# 02_PowerPart.net
KiCad netlist of a schematic drawn in EasyEDA Pro
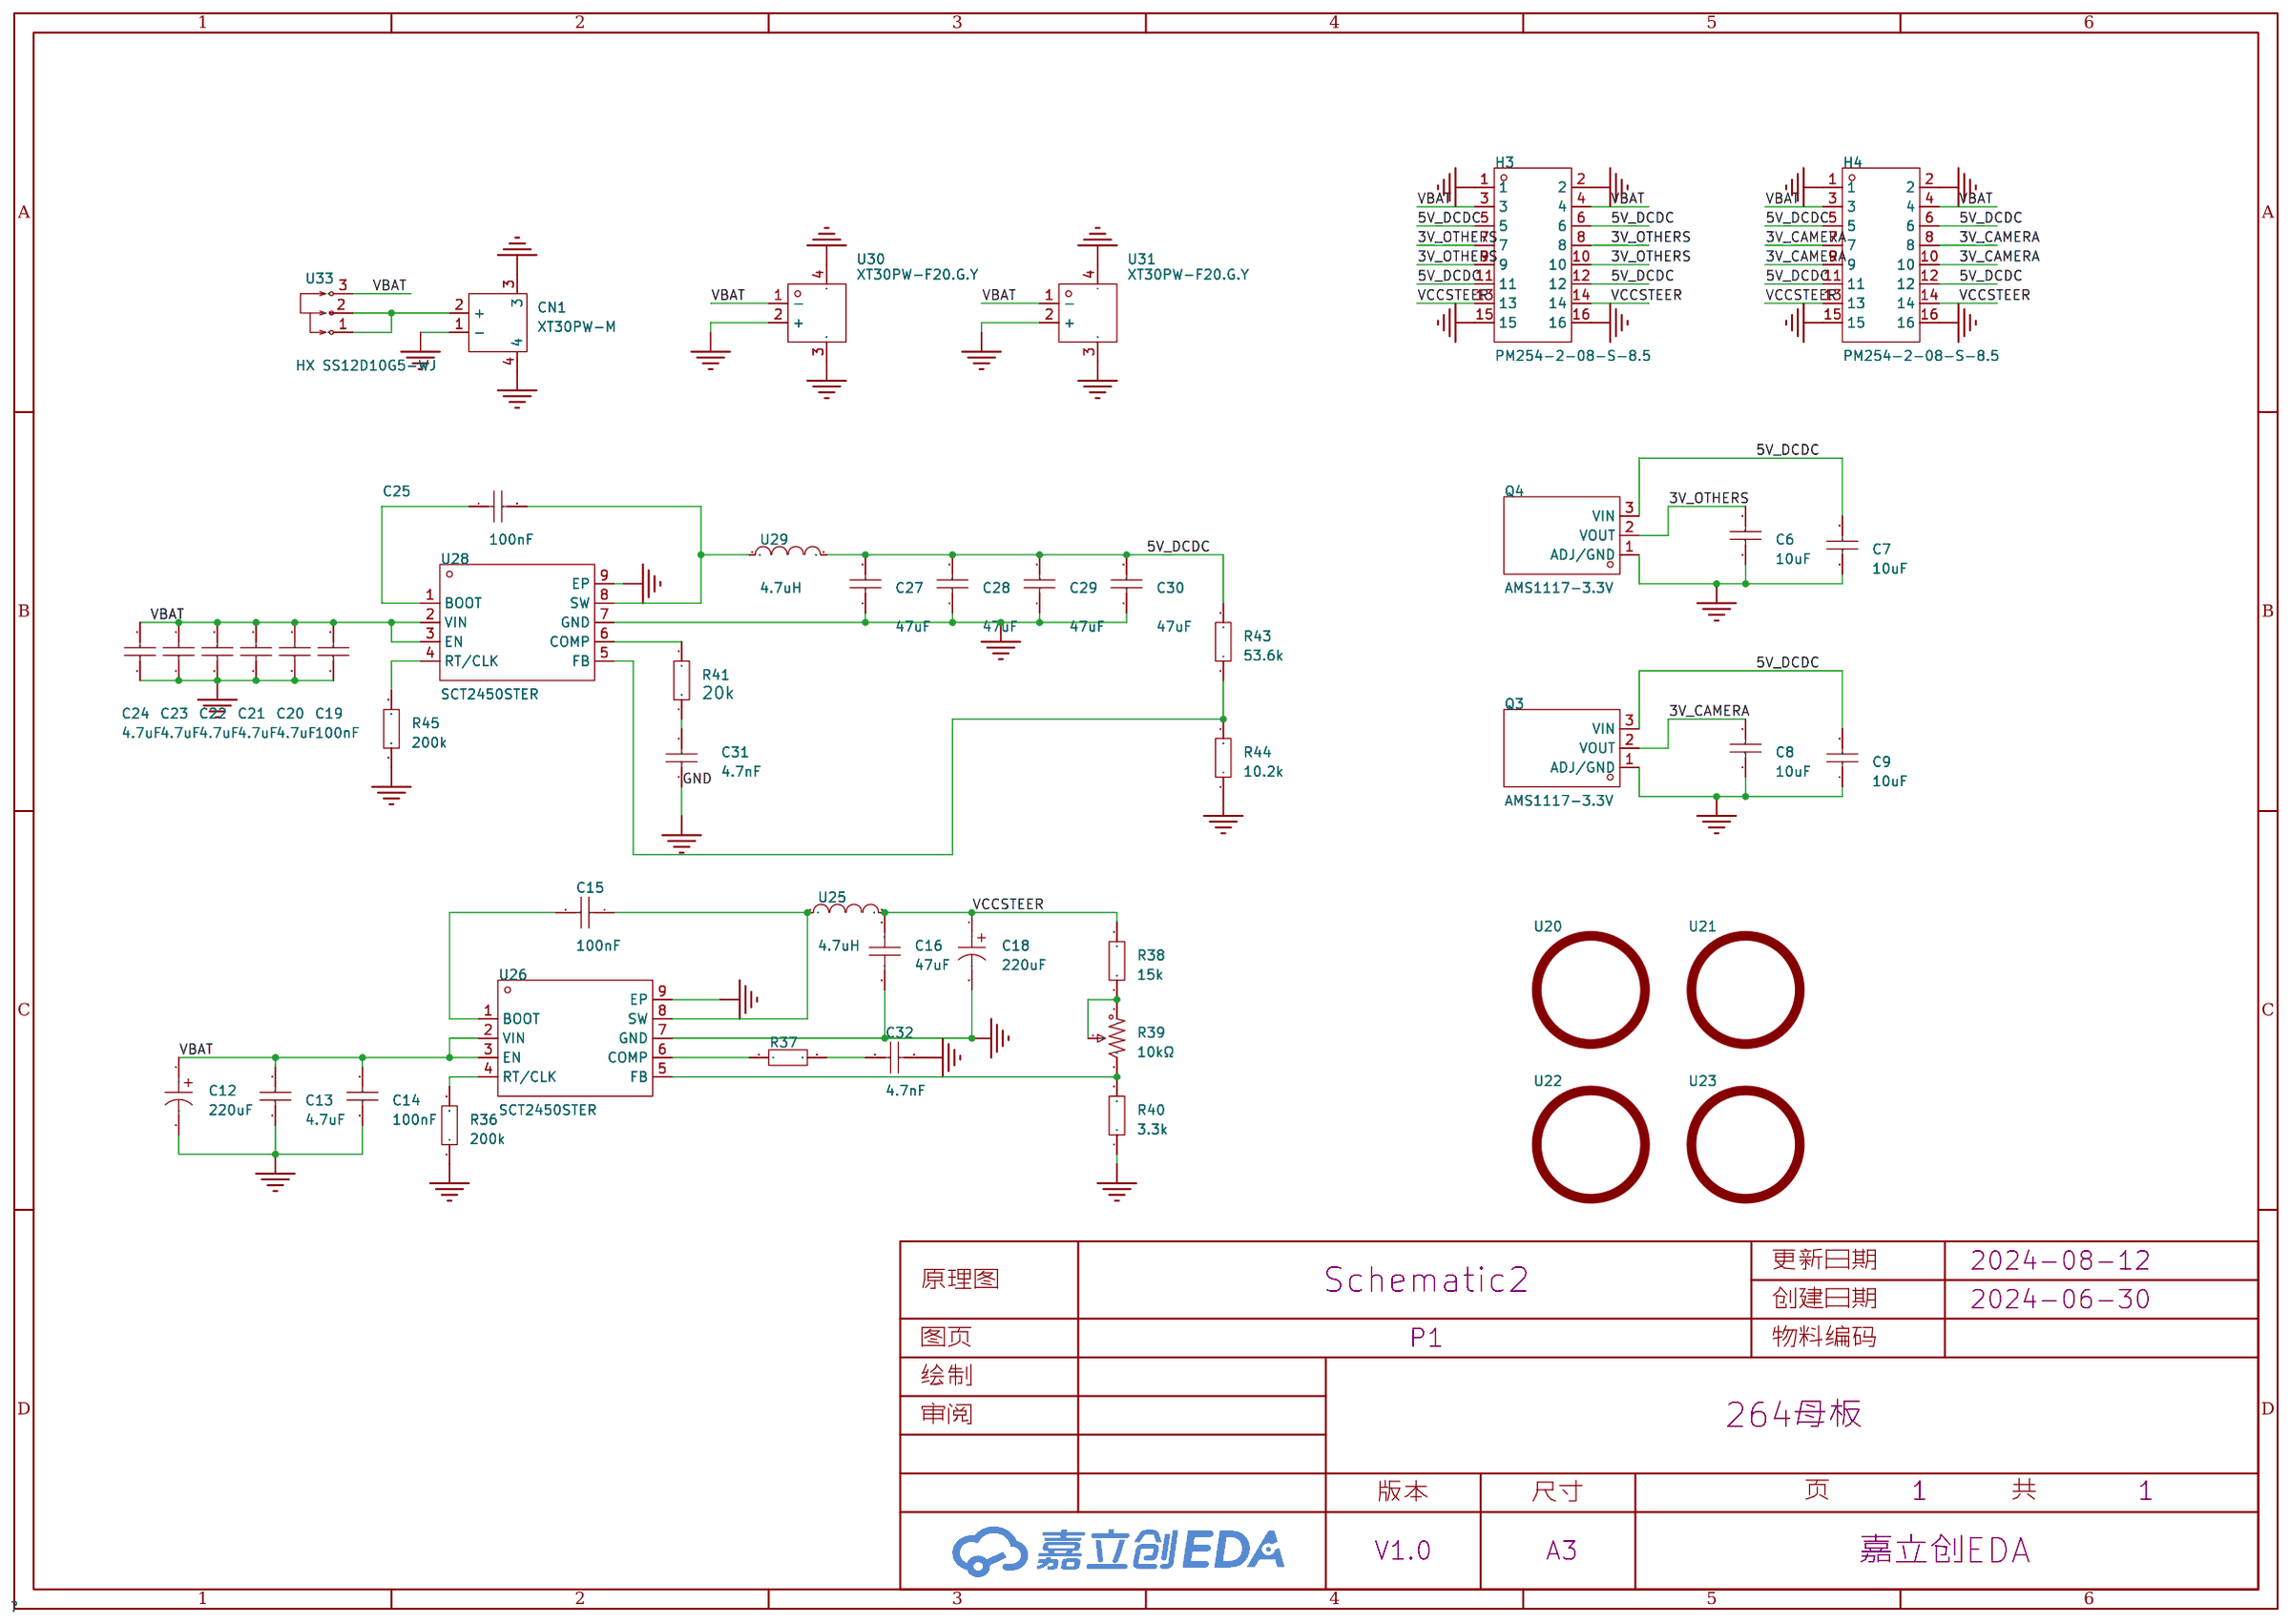
[diagram p0: schematic sheet]

(export (version "E")
  (design (tool "Eeschema 10.0.6"))
  (components
    (comp (ref "C6") (value "10uF") (footprint "easyedapro:C0805") (libsource (lib "easyedapro") (part "电容")))
    (comp (ref "C7") (value "10uF") (footprint "easyedapro:C0805") (libsource (lib "easyedapro") (part "电容")))
    (comp (ref "C8") (value "10uF") (footprint "easyedapro:C0805") (libsource (lib "easyedapro") (part "电容")))
    (comp (ref "C9") (value "10uF") (footprint "easyedapro:C0805") (libsource (lib "easyedapro") (part "电容")))
    (comp (ref "C12")
      (value "220uF")
      (footprint "easyedapro:CAP-SMD_BD6.3-L6.6-W6.6-FD")
      (description "容值:220uF;精度:±20%;额定电压:16V;纹波电流:110mA@120Hz;等效串联电阻:-;")
      (fields
        (field (name "Manufacturer Part") "RVT220UF16V67RV0015")
        (field (name "Manufacturer") "KNSCHA(科尼盛)")
      )
      (libsource (lib "easyedapro") (part "RVT220UF16V67RV0015"))
    )
    (comp (ref "C13")
      (value "4.7uF")
      (footprint "easyedapro:C0805")
      (description "50V")
      (libsource (lib "easyedapro") (part "电容-0805C"))
    )
    (comp (ref "C14")
      (value "100nF")
      (footprint "easyedapro:C0805")
      (libsource (lib "easyedapro") (part "电容-0805C"))
    )
    (comp (ref "C15")
      (value "100nF")
      (footprint "easyedapro:C0805")
      (libsource (lib "easyedapro") (part "电容-0805C"))
    )
    (comp (ref "C16")
      (value "47uF")
      (footprint "easyedapro:C1206")
      (description "容值:47uF;精度:±20%;额定电压:10V;材质(温度系数):X5R;")
      (fields
        (field (name "Manufacturer Part") "CL31A476MPHNNNE")
        (field (name "Manufacturer") "SAMSUNG(三星)")
      )
      (libsource (lib "easyedapro") (part "CL31A476MPHNNNE"))
    )
    (comp (ref "C18")
      (value "220uF")
      (footprint "easyedapro:CAP-SMD_BD6.3-L6.6-W6.6-FD")
      (description "容值:220uF;精度:±20%;额定电压:16V;纹波电流:110mA@120Hz;等效串联电阻:-;")
      (fields
        (field (name "Manufacturer Part") "RVT220UF16V67RV0015")
        (field (name "Manufacturer") "KNSCHA(科尼盛)")
      )
      (libsource (lib "easyedapro") (part "RVT220UF16V67RV0015"))
    )
    (comp (ref "C19")
      (value "100nF")
      (footprint "easyedapro:C0805")
      (libsource (lib "easyedapro") (part "电容-0805C"))
    )
    (comp (ref "C20")
      (value "4.7uF")
      (footprint "easyedapro:C0805")
      (libsource (lib "easyedapro") (part "电容-0805C"))
    )
    (comp (ref "C21")
      (value "4.7uF")
      (footprint "easyedapro:C0805")
      (libsource (lib "easyedapro") (part "电容-0805C"))
    )
    (comp (ref "C22")
      (value "4.7uF")
      (footprint "easyedapro:C0805")
      (libsource (lib "easyedapro") (part "电容-0805C"))
    )
    (comp (ref "C23")
      (value "4.7uF")
      (footprint "easyedapro:C0805")
      (libsource (lib "easyedapro") (part "电容-0805C"))
    )
    (comp (ref "C24")
      (value "4.7uF")
      (footprint "easyedapro:C0805")
      (libsource (lib "easyedapro") (part "电容-0805C"))
    )
    (comp (ref "C25")
      (value "100nF")
      (footprint "easyedapro:C0805")
      (libsource (lib "easyedapro") (part "电容-0805C"))
    )
    (comp (ref "C27")
      (value "47uF")
      (footprint "easyedapro:C0805")
      (libsource (lib "easyedapro") (part "电容-0805C"))
    )
    (comp (ref "C28")
      (value "47uF")
      (footprint "easyedapro:C0805")
      (libsource (lib "easyedapro") (part "电容-0805C"))
    )
    (comp (ref "C29")
      (value "47uF")
      (footprint "easyedapro:C0805")
      (libsource (lib "easyedapro") (part "电容-0805C"))
    )
    (comp (ref "C30")
      (value "47uF")
      (footprint "easyedapro:C0805")
      (libsource (lib "easyedapro") (part "电容-0805C"))
    )
    (comp (ref "C31")
      (value "4.7nF")
      (footprint "easyedapro:C0805")
      (libsource (lib "easyedapro") (part "电容-0805C"))
    )
    (comp (ref "C32")
      (value "4.7nF")
      (footprint "easyedapro:C0805")
      (libsource (lib "easyedapro") (part "电容-0805C"))
    )
    (comp (ref "CN1")
      (value "XT30PW-M")
      (footprint "easyedapro:CONN-TH_XT30PW-M")
      (description "类别:-;类型1:-;")
      (fields (field (name "Manufacturer") "AMASS(艾迈斯)"))
      (libsource (lib "easyedapro") (part "XT30PW-M"))
    )
    (comp (ref "H3")
      (value "PM254-2-08-S-8.5")
      (footprint "easyedapro:HDR-SMD_16P-P2.54-V-F-R2-C8-LS7.1")
      (fields (field (name "Manufacturer") "HCTL(华灿天禄)"))
      (libsource (lib "easyedapro") (part "PM254-2-08-S-8.5"))
    )
    (comp (ref "H4")
      (value "PM254-2-08-S-8.5")
      (footprint "easyedapro:HDR-SMD_16P-P2.54-V-F-R2-C8-LS7.1")
      (fields (field (name "Manufacturer") "HCTL(华灿天禄)"))
      (libsource (lib "easyedapro") (part "PM254-2-08-S-8.5"))
    )
    (comp (ref "Q3")
      (value "AMS1117-3.3V")
      (footprint "easyedapro:SOT-89-3_L4.5-W2.5-P1.50-LS4.2-BR")
      (description "输出类型:固定;最大输入电压:18V;输出电压:3.3V;最大输出电流:1A;输出极性:正极;")
      (fields (field (name "Manufacturer") "MSKSEMI(美森科)"))
      (libsource (lib "easyedapro") (part "AMS1117-3.3V_C5120796"))
    )
    (comp (ref "Q4")
      (value "AMS1117-3.3V")
      (footprint "easyedapro:SOT-89-3_L4.5-W2.5-P1.50-LS4.2-BR")
      (description "输出类型:固定;最大输入电压:18V;输出电压:3.3V;最大输出电流:1A;输出极性:正极;")
      (fields (field (name "Manufacturer") "MSKSEMI(美森科)"))
      (libsource (lib "easyedapro") (part "AMS1117-3.3V_C5120796"))
    )
    (comp (ref "R36")
      (value "200k")
      (footprint "easyedapro:R0805")
      (description "电阻类型:厚膜电阻;阻值:1kΩ;精度:±1%;功率:125mW;温度系数:±100ppm/°C;最大工作电压:150V;工作温度范围:-55°C~+155°C;")
      (libsource (lib "easyedapro") (part "电阻_0805"))
    )
    (comp (ref "R37")
      (value "20k")
      (footprint "easyedapro:R0805")
      (description "电阻类型:厚膜电阻;阻值:1kΩ;精度:±1%;功率:125mW;温度系数:±100ppm/°C;最大工作电压:150V;工作温度范围:-55°C~+155°C;")
      (libsource (lib "easyedapro") (part "电阻_0805"))
    )
    (comp (ref "R38")
      (value "15k")
      (footprint "easyedapro:R0805")
      (description "电阻类型:厚膜电阻;阻值:1kΩ;精度:±1%;功率:125mW;温度系数:±100ppm/°C;最大工作电压:150V;工作温度范围:-55°C~+155°C;")
      (libsource (lib "easyedapro") (part "电阻_0805"))
    )
    (comp (ref "R39")
      (value "10kΩ")
      (footprint "easyedapro:RES-ADJ-TH_3P-L10.0-W10.0-P2.50-L")
      (description "阻值:10kΩ;精度:±10%;")
      (fields (field (name "Manufacturer Part") "3296W-1-103") (field (name "Manufacturer") "BOCHEN(博晨)"))
      (libsource (lib "easyedapro") (part "3296W-1-103"))
    )
    (comp (ref "R40")
      (value "3.3k")
      (footprint "easyedapro:R0805")
      (description "电阻类型:厚膜电阻;阻值:1kΩ;精度:±1%;功率:125mW;温度系数:±100ppm/°C;最大工作电压:150V;工作温度范围:-55°C~+155°C;")
      (libsource (lib "easyedapro") (part "电阻_0805"))
    )
    (comp (ref "R41")
      (value "20k")
      (footprint "easyedapro:R0805")
      (description "电阻类型:厚膜电阻;阻值:1kΩ;精度:±1%;功率:125mW;温度系数:±100ppm/°C;最大工作电压:150V;工作温度范围:-55°C~+155°C;")
      (libsource (lib "easyedapro") (part "电阻_0805"))
    )
    (comp (ref "R43")
      (value "53.6k")
      (footprint "easyedapro:R0603")
      (description "电阻类型:厚膜电阻;阻值:10kΩ;精度:±1%;功率:100mW;最大工作电压:75V;温度系数:±100ppm/°C;")
      (fields
        (field (name "Manufacturer Part") "0603WAF1002T5E")
        (field (name "Manufacturer") "UNI-ROYAL(厚声)")
      )
      (libsource (lib "easyedapro") (part "0603WAF1002T5E"))
    )
    (comp (ref "R44")
      (value "10.2k")
      (footprint "easyedapro:R0603")
      (description "电阻类型:厚膜电阻;阻值:10kΩ;精度:±1%;功率:100mW;最大工作电压:75V;温度系数:±100ppm/°C;")
      (fields
        (field (name "Manufacturer Part") "0603WAF1002T5E")
        (field (name "Manufacturer") "UNI-ROYAL(厚声)")
      )
      (libsource (lib "easyedapro") (part "0603WAF1002T5E"))
    )
    (comp (ref "R45")
      (value "200k")
      (footprint "easyedapro:R0805")
      (description "电阻类型:厚膜电阻;阻值:1kΩ;精度:±1%;功率:125mW;温度系数:±100ppm/°C;最大工作电压:150V;工作温度范围:-55°C~+155°C;")
      (libsource (lib "easyedapro") (part "电阻_0805"))
    )
    (comp (ref "U20") (value "~") (footprint "easyedapro:固定孔") (libsource (lib "easyedapro") (part "固定孔")))
    (comp (ref "U21") (value "~") (footprint "easyedapro:固定孔") (libsource (lib "easyedapro") (part "固定孔")))
    (comp (ref "U22") (value "~") (footprint "easyedapro:固定孔") (libsource (lib "easyedapro") (part "固定孔")))
    (comp (ref "U23") (value "~") (footprint "easyedapro:固定孔") (libsource (lib "easyedapro") (part "固定孔")))
    (comp (ref "U25")
      (value "4.7uH")
      (footprint "easyedapro:IND-SMD_L7.2-W6.6_GPSR07X0")
      (description "电感值:4.7uH;精度:±20%;额定电流:5A;直流电阻(DCR):34.5mΩ;")
      (fields (field (name "Manufacturer Part") "CYA0630-4.7UH") (field (name "Manufacturer") "SHOU HAN(首韩)"))
      (libsource (lib "easyedapro") (part "CYA0630-4.7UH"))
    )
    (comp (ref "U26")
      (value "SCT2450STER")
      (footprint "easyedapro:ESOP-8_L4.9-W3.9-P1.27-LS6.0-BL-EP")
      (fields (field (name "Manufacturer") "SCT(芯洲科技)"))
      (libsource (lib "easyedapro") (part "SCT2450STER"))
    )
    (comp (ref "U28")
      (value "SCT2450STER")
      (footprint "easyedapro:ESOP-8_L4.9-W3.9-P1.27-LS6.0-BL-EP")
      (fields (field (name "Manufacturer") "SCT(芯洲科技)"))
      (libsource (lib "easyedapro") (part "SCT2450STER"))
    )
    (comp (ref "U29")
      (value "4.7uH")
      (footprint "easyedapro:IND-SMD_L7.2-W6.6_GPSR07X0")
      (description "电感值:4.7uH;精度:±20%;额定电流:5A;直流电阻(DCR):34.5mΩ;")
      (fields (field (name "Manufacturer Part") "CYA0630-4.7UH") (field (name "Manufacturer") "SHOU HAN(首韩)"))
      (libsource (lib "easyedapro") (part "CYA0630-4.7UH"))
    )
    (comp (ref "U30")
      (value "XT30PW-F20.G.Y")
      (footprint "easyedapro:CONN-TH_XT30PW-F-1")
      (description "类别:-;类型1:-;")
      (fields (field (name "Manufacturer") "AMASS(艾迈斯)"))
      (libsource (lib "easyedapro") (part "XT30PW-F20.G.Y"))
    )
    (comp (ref "U31")
      (value "XT30PW-F20.G.Y")
      (footprint "easyedapro:CONN-TH_XT30PW-F-1")
      (description "类别:-;类型1:-;")
      (fields (field (name "Manufacturer") "AMASS(艾迈斯)"))
      (libsource (lib "easyedapro") (part "XT30PW-F20.G.Y"))
    )
    (comp (ref "U33")
      (value "HX SS12D10G5-WJ")
      (footprint "easyedapro:SW-TH_3P-P4.80_HX-SS12D10G5-WJ")
      (description "电路结构:单刀双掷;额定电流(DC):2A;额定电压(DC):125V;机械寿命:3千次;")
      (fields (field (name "Manufacturer") "hanxia(韩下)"))
      (libsource (lib "easyedapro") (part "HX SS12D10G5-WJ"))
    )
  )
  (nets
    (net (code "1") (name "/3V_CAMERA") (class "Default")
      (node (ref "C8") (pin "2") (pinfunction "2_2") (pintype "input"))
      (node (ref "H4") (pin "10") (pinfunction "10_10") (pintype "unspecified"))
      (node (ref "H4") (pin "7") (pinfunction "7_7") (pintype "unspecified"))
      (node (ref "H4") (pin "8") (pinfunction "8_8") (pintype "unspecified"))
      (node (ref "H4") (pin "9") (pinfunction "9_9") (pintype "unspecified"))
      (node (ref "Q3") (pin "2") (pinfunction "VOUT_2") (pintype "unspecified"))
    )
    (net (code "2") (name "/3V_OTHERS") (class "Default")
      (node (ref "C6") (pin "2") (pinfunction "2_2") (pintype "input"))
      (node (ref "H3") (pin "10") (pinfunction "10_10") (pintype "unspecified"))
      (node (ref "H3") (pin "7") (pinfunction "7_7") (pintype "unspecified"))
      (node (ref "H3") (pin "8") (pinfunction "8_8") (pintype "unspecified"))
      (node (ref "H3") (pin "9") (pinfunction "9_9") (pintype "unspecified"))
      (node (ref "Q4") (pin "2") (pinfunction "VOUT_2") (pintype "unspecified"))
    )
    (net (code "3") (name "/5V_DCDC") (class "Default")
      (node (ref "C27") (pin "2") (pinfunction "2_2") (pintype "input"))
      (node (ref "C28") (pin "2") (pinfunction "2_2") (pintype "input"))
      (node (ref "C29") (pin "2") (pinfunction "2_2") (pintype "input"))
      (node (ref "C30") (pin "2") (pinfunction "2_2") (pintype "input"))
      (node (ref "C7") (pin "2") (pinfunction "2_2") (pintype "input"))
      (node (ref "C9") (pin "2") (pinfunction "2_2") (pintype "input"))
      (node (ref "H3") (pin "11") (pinfunction "11_11") (pintype "unspecified"))
      (node (ref "H3") (pin "12") (pinfunction "12_12") (pintype "unspecified"))
      (node (ref "H3") (pin "5") (pinfunction "5_5") (pintype "unspecified"))
      (node (ref "H3") (pin "6") (pinfunction "6_6") (pintype "unspecified"))
      (node (ref "H4") (pin "11") (pinfunction "11_11") (pintype "unspecified"))
      (node (ref "H4") (pin "12") (pinfunction "12_12") (pintype "unspecified"))
      (node (ref "H4") (pin "5") (pinfunction "5_5") (pintype "unspecified"))
      (node (ref "H4") (pin "6") (pinfunction "6_6") (pintype "unspecified"))
      (node (ref "Q3") (pin "3") (pinfunction "VIN_3") (pintype "unspecified"))
      (node (ref "Q4") (pin "3") (pinfunction "VIN_3") (pintype "unspecified"))
      (node (ref "R43") (pin "2") (pinfunction "2_2") (pintype "input"))
      (node (ref "U29") (pin "2") (pinfunction "2_2") (pintype "unspecified"))
    )
    (net (code "4") (name "/VBAT") (class "Default")
      (node (ref "C12") (pin "1") (pinfunction "1_1") (pintype "input"))
      (node (ref "C13") (pin "2") (pinfunction "2_2") (pintype "input"))
      (node (ref "C14") (pin "2") (pinfunction "2_2") (pintype "input"))
      (node (ref "C19") (pin "1") (pinfunction "1_1") (pintype "input"))
      (node (ref "C20") (pin "1") (pinfunction "1_1") (pintype "input"))
      (node (ref "C21") (pin "1") (pinfunction "1_1") (pintype "input"))
      (node (ref "C22") (pin "1") (pinfunction "1_1") (pintype "input"))
      (node (ref "C23") (pin "1") (pinfunction "1_1") (pintype "input"))
      (node (ref "C24") (pin "1") (pinfunction "1_1") (pintype "input"))
      (node (ref "H3") (pin "3") (pinfunction "3_3") (pintype "unspecified"))
      (node (ref "H3") (pin "4") (pinfunction "4_4") (pintype "unspecified"))
      (node (ref "H4") (pin "3") (pinfunction "3_3") (pintype "unspecified"))
      (node (ref "H4") (pin "4") (pinfunction "4_4") (pintype "unspecified"))
      (node (ref "U26") (pin "2") (pinfunction "VIN_2") (pintype "input"))
      (node (ref "U26") (pin "3") (pinfunction "EN_3") (pintype "input"))
      (node (ref "U28") (pin "2") (pinfunction "VIN_2") (pintype "input"))
      (node (ref "U28") (pin "3") (pinfunction "EN_3") (pintype "input"))
      (node (ref "U30") (pin "1") (pinfunction "-_1") (pintype "unspecified"))
      (node (ref "U31") (pin "1") (pinfunction "-_1") (pintype "unspecified"))
      (node (ref "U33") (pin "3") (pinfunction "3_3") (pintype "unspecified"))
    )
    (net (code "5") (name "/VCCSTEER") (class "Default")
      (node (ref "C16") (pin "2") (pinfunction "2_2") (pintype "unspecified"))
      (node (ref "C18") (pin "1") (pinfunction "1_1") (pintype "input"))
      (node (ref "H3") (pin "13") (pinfunction "13_13") (pintype "unspecified"))
      (node (ref "H3") (pin "14") (pinfunction "14_14") (pintype "unspecified"))
      (node (ref "H4") (pin "13") (pinfunction "13_13") (pintype "unspecified"))
      (node (ref "H4") (pin "14") (pinfunction "14_14") (pintype "unspecified"))
      (node (ref "R38") (pin "2") (pinfunction "2_2") (pintype "input"))
      (node (ref "U25") (pin "2") (pinfunction "2_2") (pintype "unspecified"))
    )
    (net (code "6") (name "GND") (class "Default")
      (node (ref "C12") (pin "2") (pinfunction "2_2") (pintype "input"))
      (node (ref "C13") (pin "1") (pinfunction "1_1") (pintype "input"))
      (node (ref "C14") (pin "1") (pinfunction "1_1") (pintype "input"))
      (node (ref "C16") (pin "1") (pinfunction "1_1") (pintype "unspecified"))
      (node (ref "C18") (pin "2") (pinfunction "2_2") (pintype "input"))
      (node (ref "C19") (pin "2") (pinfunction "2_2") (pintype "input"))
      (node (ref "C20") (pin "2") (pinfunction "2_2") (pintype "input"))
      (node (ref "C21") (pin "2") (pinfunction "2_2") (pintype "input"))
      (node (ref "C22") (pin "2") (pinfunction "2_2") (pintype "input"))
      (node (ref "C23") (pin "2") (pinfunction "2_2") (pintype "input"))
      (node (ref "C24") (pin "2") (pinfunction "2_2") (pintype "input"))
      (node (ref "C27") (pin "1") (pinfunction "1_1") (pintype "input"))
      (node (ref "C28") (pin "1") (pinfunction "1_1") (pintype "input"))
      (node (ref "C29") (pin "1") (pinfunction "1_1") (pintype "input"))
      (node (ref "C30") (pin "1") (pinfunction "1_1") (pintype "input"))
      (node (ref "C31") (pin "2") (pinfunction "2_2") (pintype "input"))
      (node (ref "C32") (pin "2") (pinfunction "2_2") (pintype "input"))
      (node (ref "C6") (pin "1") (pinfunction "1_1") (pintype "input"))
      (node (ref "C7") (pin "1") (pinfunction "1_1") (pintype "input"))
      (node (ref "C8") (pin "1") (pinfunction "1_1") (pintype "input"))
      (node (ref "C9") (pin "1") (pinfunction "1_1") (pintype "input"))
      (node (ref "CN1") (pin "1") (pinfunction "-_1") (pintype "unspecified"))
      (node (ref "CN1") (pin "3") (pinfunction "3_3") (pintype "unspecified"))
      (node (ref "CN1") (pin "4") (pinfunction "4_4") (pintype "unspecified"))
      (node (ref "H3") (pin "1") (pinfunction "1_1") (pintype "unspecified"))
      (node (ref "H3") (pin "15") (pinfunction "15_15") (pintype "unspecified"))
      (node (ref "H3") (pin "16") (pinfunction "16_16") (pintype "unspecified"))
      (node (ref "H3") (pin "2") (pinfunction "2_2") (pintype "unspecified"))
      (node (ref "H4") (pin "1") (pinfunction "1_1") (pintype "unspecified"))
      (node (ref "H4") (pin "15") (pinfunction "15_15") (pintype "unspecified"))
      (node (ref "H4") (pin "16") (pinfunction "16_16") (pintype "unspecified"))
      (node (ref "H4") (pin "2") (pinfunction "2_2") (pintype "unspecified"))
      (node (ref "Q3") (pin "1") (pinfunction "ADJ/GND_1") (pintype "unspecified"))
      (node (ref "Q4") (pin "1") (pinfunction "ADJ/GND_1") (pintype "unspecified"))
      (node (ref "R36") (pin "1") (pinfunction "1_1") (pintype "input"))
      (node (ref "R40") (pin "1") (pinfunction "1_1") (pintype "input"))
      (node (ref "R44") (pin "1") (pinfunction "1_1") (pintype "input"))
      (node (ref "R45") (pin "1") (pinfunction "1_1") (pintype "input"))
      (node (ref "U26") (pin "7") (pinfunction "GND_7") (pintype "input"))
      (node (ref "U26") (pin "9") (pinfunction "EP_9") (pintype "input"))
      (node (ref "U28") (pin "7") (pinfunction "GND_7") (pintype "input"))
      (node (ref "U28") (pin "9") (pinfunction "EP_9") (pintype "input"))
      (node (ref "U30") (pin "2") (pinfunction "+_2") (pintype "unspecified"))
      (node (ref "U30") (pin "3") (pinfunction "3_3") (pintype "unspecified"))
      (node (ref "U30") (pin "4") (pinfunction "4_4") (pintype "unspecified"))
      (node (ref "U31") (pin "2") (pinfunction "+_2") (pintype "unspecified"))
      (node (ref "U31") (pin "3") (pinfunction "3_3") (pintype "unspecified"))
      (node (ref "U31") (pin "4") (pinfunction "4_4") (pintype "unspecified"))
    )
    (net (code "7") (name "Net-(C31-Pad1)") (class "Default")
      (node (ref "C31") (pin "1") (pinfunction "1_1") (pintype "input"))
      (node (ref "R41") (pin "1") (pinfunction "1_1") (pintype "input"))
    )
    (net (code "8") (name "Net-(C32-Pad1)") (class "Default")
      (node (ref "C32") (pin "1") (pinfunction "1_1") (pintype "input"))
      (node (ref "R37") (pin "2") (pinfunction "2_2") (pintype "input"))
    )
    (net (code "9") (name "Net-(CN1-+)") (class "Default")
      (node (ref "CN1") (pin "2") (pinfunction "+_2") (pintype "unspecified"))
      (node (ref "U33") (pin "1") (pinfunction "1_1") (pintype "unspecified"))
      (node (ref "U33") (pin "2") (pinfunction "2_2") (pintype "unspecified"))
    )
    (net (code "10") (name "Net-(R38-Pad1)") (class "Default")
      (node (ref "R38") (pin "1") (pinfunction "1_1") (pintype "input"))
      (node (ref "R39") (pin "1") (pinfunction "1_1") (pintype "input"))
      (node (ref "R39") (pin "2") (pinfunction "2_2") (pintype "input"))
    )
    (net (code "11") (name "Net-(U26-BOOT)") (class "Default")
      (node (ref "C15") (pin "2") (pinfunction "2_2") (pintype "input"))
      (node (ref "U26") (pin "1") (pinfunction "BOOT_1") (pintype "input"))
    )
    (net (code "12") (name "Net-(U26-COMP)") (class "Default")
      (node (ref "R37") (pin "1") (pinfunction "1_1") (pintype "input"))
      (node (ref "U26") (pin "6") (pinfunction "COMP_6") (pintype "input"))
    )
    (net (code "13") (name "Net-(U26-FB)") (class "Default")
      (node (ref "R39") (pin "3") (pinfunction "3_3") (pintype "input"))
      (node (ref "R40") (pin "2") (pinfunction "2_2") (pintype "input"))
      (node (ref "U26") (pin "5") (pinfunction "FB_5") (pintype "input"))
    )
    (net (code "14") (name "Net-(U26-RT{slash}CLK)") (class "Default")
      (node (ref "R36") (pin "2") (pinfunction "2_2") (pintype "input"))
      (node (ref "U26") (pin "4") (pinfunction "RT/CLK_4") (pintype "input"))
    )
    (net (code "15") (name "Net-(U26-SW)") (class "Default")
      (node (ref "C15") (pin "1") (pinfunction "1_1") (pintype "input"))
      (node (ref "U25") (pin "1") (pinfunction "1_1") (pintype "unspecified"))
      (node (ref "U26") (pin "8") (pinfunction "SW_8") (pintype "input"))
    )
    (net (code "16") (name "Net-(U28-BOOT)") (class "Default")
      (node (ref "C25") (pin "1") (pinfunction "1_1") (pintype "input"))
      (node (ref "U28") (pin "1") (pinfunction "BOOT_1") (pintype "input"))
    )
    (net (code "17") (name "Net-(U28-COMP)") (class "Default")
      (node (ref "R41") (pin "2") (pinfunction "2_2") (pintype "input"))
      (node (ref "U28") (pin "6") (pinfunction "COMP_6") (pintype "input"))
    )
    (net (code "18") (name "Net-(U28-FB)") (class "Default")
      (node (ref "R43") (pin "1") (pinfunction "1_1") (pintype "input"))
      (node (ref "R44") (pin "2") (pinfunction "2_2") (pintype "input"))
      (node (ref "U28") (pin "5") (pinfunction "FB_5") (pintype "input"))
    )
    (net (code "19") (name "Net-(U28-RT{slash}CLK)") (class "Default")
      (node (ref "R45") (pin "2") (pinfunction "2_2") (pintype "input"))
      (node (ref "U28") (pin "4") (pinfunction "RT/CLK_4") (pintype "input"))
    )
    (net (code "20") (name "Net-(U28-SW)") (class "Default")
      (node (ref "C25") (pin "2") (pinfunction "2_2") (pintype "input"))
      (node (ref "U28") (pin "8") (pinfunction "SW_8") (pintype "input"))
      (node (ref "U29") (pin "1") (pinfunction "1_1") (pintype "unspecified"))
    )
  )
)
